# OpenPack_BATMOD_V1p0_USBC.net
KiCad netlist of a schematic drawn in Altium Designer
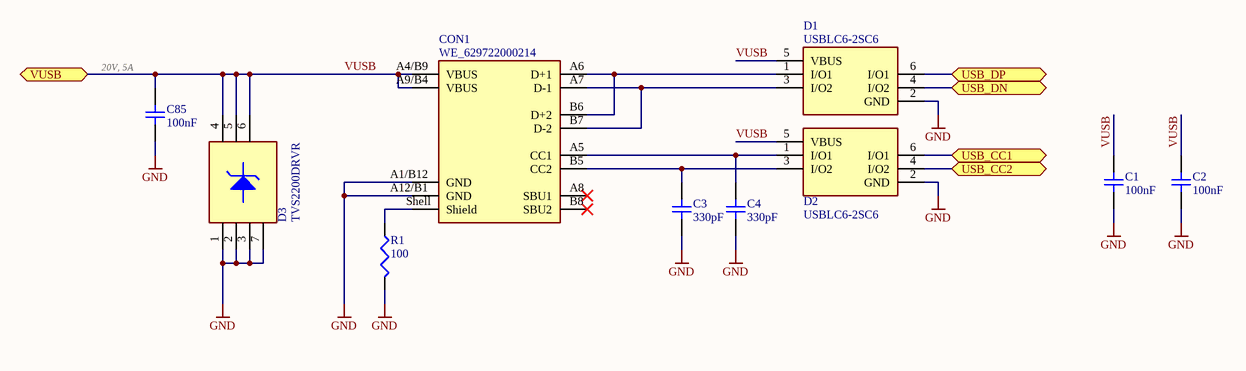
[diagram p0: OpenPack_BATMOD_V1p0_USBC.SchDoc]

(export (version "E")
  (design (tool "Eeschema 10.0.6"))
  (components
    (comp (ref "C1")
      (value "100nF")
      (footprint "CAP_0603")
      (description "MLCC capacitor")
      (libsource (lib "SCHLIB") (part "NP-CAPACITOR"))
    )
    (comp (ref "C2")
      (value "100nF")
      (footprint "CAP_0603")
      (description "MLCC capacitor")
      (libsource (lib "SCHLIB") (part "NP-CAPACITOR"))
    )
    (comp (ref "C3")
      (value "330pF")
      (footprint "CAP_0603")
      (description "MLCC capacitor")
      (libsource (lib "SCHLIB") (part "NP-CAPACITOR"))
    )
    (comp (ref "C4")
      (value "330pF")
      (footprint "CAP_0603")
      (description "MLCC capacitor")
      (libsource (lib "SCHLIB") (part "NP-CAPACITOR"))
    )
    (comp (ref "C85")
      (value "100nF")
      (footprint "CAP_0603")
      (description "MLCC capacitor")
      (libsource (lib "SCHLIB") (part "NP-CAPACITOR"))
    )
    (comp (ref "CON1")
      (value "WE_629722000214")
      (footprint "WE_629722000214")
      (description "USB Connectors WR-COM Receptacle USB 2.0 Type C Horizontal SMT 16 pins- PCB Thickness 0.8mm")
      (fields (field (name "PART NUMBER") "710-629722000214"))
      (libsource (lib "SCHLIB") (part "WE_629722000214"))
    )
    (comp (ref "D1")
      (value "USBLC6-2SC6")
      (footprint "SOT-23-6")
      (description "ESD Protection Diodes / TVS Diodes ESD Protection Low Cap")
      (fields (field (name "PART NUMBER") "511-USBLC6-2SC6"))
      (libsource (lib "SCHLIB") (part "USBLC6-2SC6"))
    )
    (comp (ref "D2")
      (value "USBLC6-2SC6")
      (footprint "SOT-23-6")
      (description "ESD Protection Diodes / TVS Diodes ESD Protection Low Cap")
      (fields (field (name "PART NUMBER") "511-USBLC6-2SC6"))
      (libsource (lib "SCHLIB") (part "USBLC6-2SC6"))
    )
    (comp (ref "D3")
      (value "TVS2200DRVR")
      (footprint "WSON-6")
      (description "ESD Protection Diodes / TVS Diodes 22V flat-clamp surge protection device 6")
      (fields (field (name "PART NUMBER") "595-TVS2200DRVR"))
      (libsource (lib "SCHLIB") (part "TVS2200DRVR"))
    )
    (comp (ref "R1")
      (value "100")
      (footprint "RES-0603")
      (description "Metal Film Resistor")
      (libsource (lib "SCHLIB") (part "RESISTOR"))
    )
  )
  (nets
    (net (code "1") (name "/USB_CC1") (class "Default")
      (node (ref "D2") (pin "6") (pinfunction "I/O1_6") (pintype "passive"))
    )
    (net (code "2") (name "/USB_CC2") (class "Default")
      (node (ref "D2") (pin "4") (pinfunction "I/O2_4") (pintype "passive"))
    )
    (net (code "3") (name "/USB_DN") (class "Default")
      (node (ref "D1") (pin "4") (pinfunction "I/O2_4") (pintype "passive"))
    )
    (net (code "4") (name "/USB_DP") (class "Default")
      (node (ref "D1") (pin "6") (pinfunction "I/O1_6") (pintype "passive"))
    )
    (net (code "5") (name "/VUSB") (class "Default")
      (node (ref "C1") (pin "2") (pinfunction "2_2") (pintype "passive"))
      (node (ref "C2") (pin "2") (pinfunction "2_2") (pintype "passive"))
      (node (ref "C85") (pin "2") (pinfunction "2_2") (pintype "passive"))
      (node (ref "CON1") (pin "A4/B9") (pinfunction "VBUS_A4/B9") (pintype "passive"))
      (node (ref "CON1") (pin "A9/B4") (pinfunction "VBUS_A9/B4") (pintype "passive"))
      (node (ref "D1") (pin "5") (pinfunction "VBUS_5") (pintype "passive"))
      (node (ref "D2") (pin "5") (pinfunction "VBUS_5") (pintype "passive"))
      (node (ref "D3") (pin "4") (pinfunction "IN_4") (pintype "passive"))
      (node (ref "D3") (pin "5") (pinfunction "IN_5") (pintype "passive"))
      (node (ref "D3") (pin "6") (pinfunction "IN_6") (pintype "passive"))
    )
    (net (code "6") (name "GND") (class "Default")
      (node (ref "C1") (pin "1") (pinfunction "1_1") (pintype "passive"))
      (node (ref "C2") (pin "1") (pinfunction "1_1") (pintype "passive"))
      (node (ref "C3") (pin "1") (pinfunction "1_1") (pintype "passive"))
      (node (ref "C4") (pin "1") (pinfunction "1_1") (pintype "passive"))
      (node (ref "C85") (pin "1") (pinfunction "1_1") (pintype "passive"))
      (node (ref "CON1") (pin "A1/B12") (pinfunction "GND_A1/B12") (pintype "passive"))
      (node (ref "CON1") (pin "A12/B1") (pinfunction "GND_A12/B1") (pintype "passive"))
      (node (ref "D1") (pin "2") (pinfunction "GND_2") (pintype "passive"))
      (node (ref "D2") (pin "2") (pinfunction "GND_2") (pintype "passive"))
      (node (ref "D3") (pin "1") (pinfunction "GND_1") (pintype "passive"))
      (node (ref "D3") (pin "2") (pinfunction "GND_2") (pintype "passive"))
      (node (ref "D3") (pin "3") (pinfunction "GND_3") (pintype "passive"))
      (node (ref "D3") (pin "7") (pinfunction "GND_7") (pintype "passive"))
      (node (ref "R1") (pin "2") (pintype "passive"))
    )
    (net (code "7") (name "Net-(CON1-CC1)") (class "Default")
      (node (ref "C4") (pin "2") (pinfunction "2_2") (pintype "passive"))
      (node (ref "CON1") (pin "A5") (pinfunction "CC1_A5") (pintype "passive"))
      (node (ref "D2") (pin "1") (pinfunction "I/O1_1") (pintype "passive"))
    )
    (net (code "8") (name "Net-(CON1-CC2)") (class "Default")
      (node (ref "C3") (pin "2") (pinfunction "2_2") (pintype "passive"))
      (node (ref "CON1") (pin "B5") (pinfunction "CC2_B5") (pintype "passive"))
      (node (ref "D2") (pin "3") (pinfunction "I/O2_3") (pintype "passive"))
    )
    (net (code "9") (name "Net-(CON1-D+1)") (class "Default")
      (node (ref "CON1") (pin "A6") (pinfunction "D+1_A6") (pintype "passive"))
      (node (ref "CON1") (pin "B6") (pinfunction "D+2_B6") (pintype "passive"))
      (node (ref "D1") (pin "1") (pinfunction "I/O1_1") (pintype "passive"))
    )
    (net (code "10") (name "Net-(CON1-D-1)") (class "Default")
      (node (ref "CON1") (pin "A7") (pinfunction "D-1_A7") (pintype "passive"))
      (node (ref "CON1") (pin "B7") (pinfunction "D-2_B7") (pintype "passive"))
      (node (ref "D1") (pin "3") (pinfunction "I/O2_3") (pintype "passive"))
    )
    (net (code "11") (name "Net-(CON1-Shield)") (class "Default")
      (node (ref "CON1") (pin "Shell") (pinfunction "Shield_Shell") (pintype "passive"))
      (node (ref "R1") (pin "1") (pintype "passive"))
    )
    (net (code "12") (name "unconnected-(CON1-SBU1-PadA8)") (class "Default")
      (node (ref "CON1") (pin "A8") (pinfunction "SBU1_A8") (pintype "passive+no_connect"))
    )
    (net (code "13") (name "unconnected-(CON1-SBU2-PadB8)") (class "Default")
      (node (ref "CON1") (pin "B8") (pinfunction "SBU2_B8") (pintype "passive+no_connect"))
    )
  )
)
